# 02_Power.net
KiCad netlist of a schematic drawn in Altium Designer
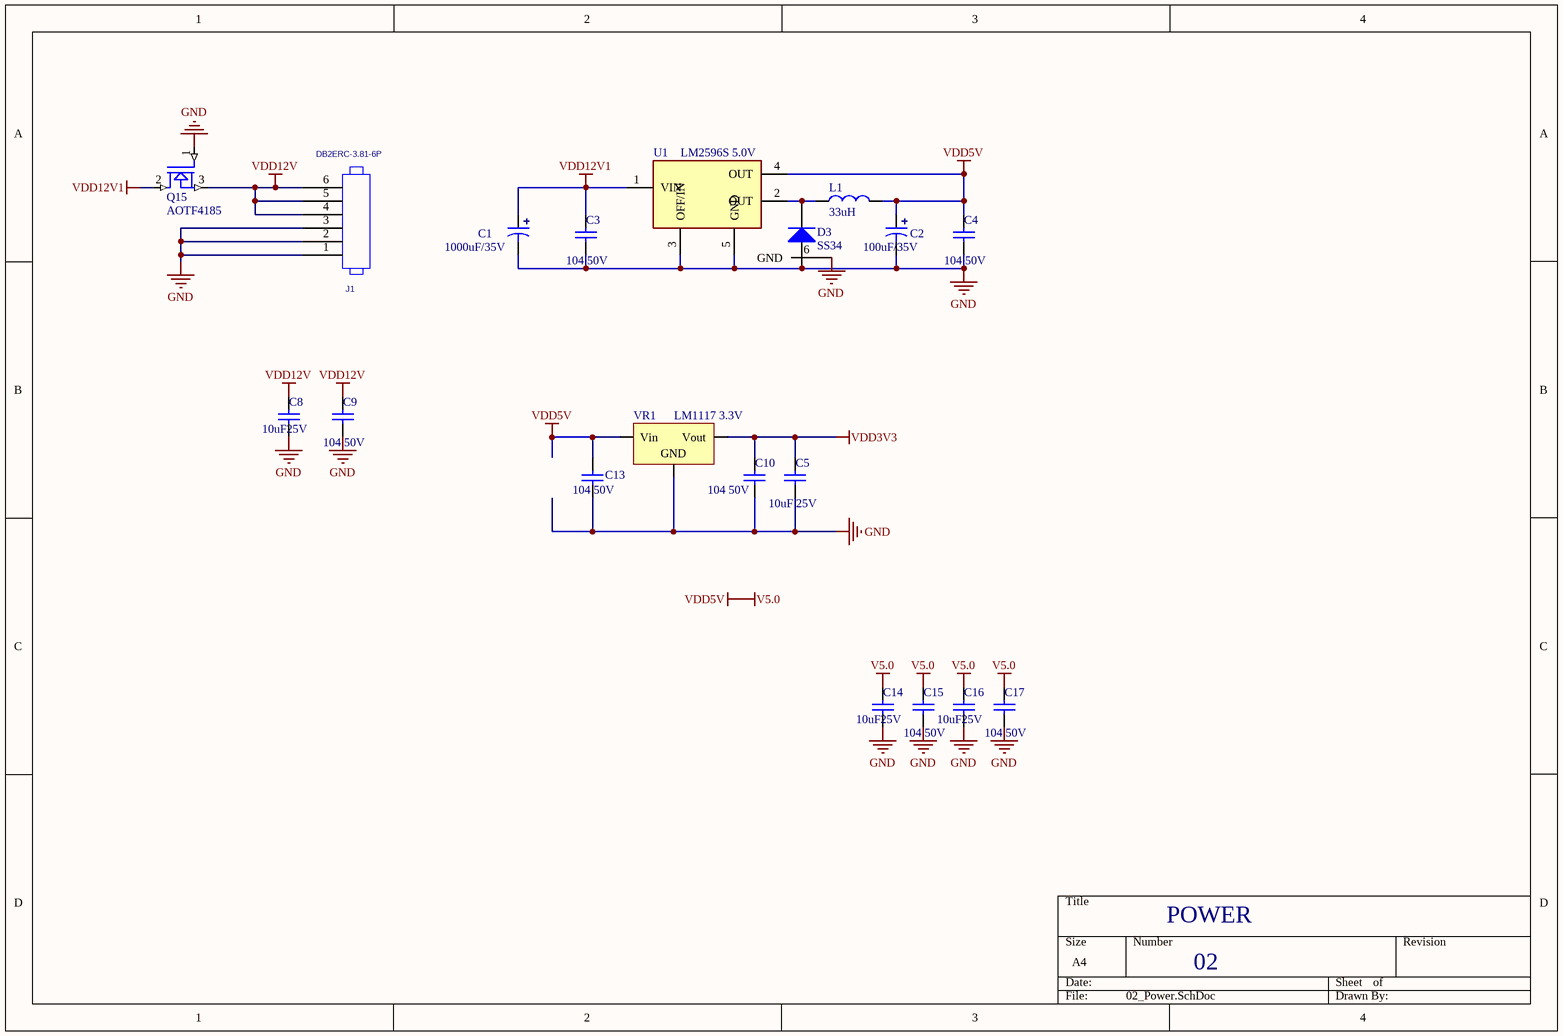
[diagram p0: 02_Power.SchDoc]

(export (version "E")
  (design (tool "Eeschema 10.0.6"))
  (components
    (comp (ref "C1")
      (value "1000uF/35V")
      (footprint "10*16")
      (description "电解电容")
      (libsource (lib "XiaoyI") (part "CAP2"))
    )
    (comp (ref "C2")
      (value "100uF/35V")
      (footprint "6*8")
      (description "电解电容")
      (libsource (lib "XiaoyI") (part "CAP2"))
    )
    (comp (ref "C3")
      (value "104 50V")
      (footprint "SMD-0805C")
      (description "贴片电容 10%")
      (libsource (lib "XiaoyI") (part "CAP4"))
    )
    (comp (ref "C4")
      (value "104 50V")
      (footprint "SMD-0805C")
      (description "贴片电容 10%")
      (libsource (lib "XiaoyI") (part "CAP4"))
    )
    (comp (ref "C5")
      (value "10uF 25V")
      (footprint "SMD-0603C")
      (description "贴片电容 20%")
      (libsource (lib "XiaoyI") (part "CAP4"))
    )
    (comp (ref "C8")
      (value "10uF25V")
      (footprint "SMD-0603C")
      (description "贴片电容 10%")
      (libsource (lib "XiaoyI") (part "CAP4"))
    )
    (comp (ref "C9")
      (value "104 50V")
      (footprint "SMD-0603C")
      (description "贴片电容 10%")
      (libsource (lib "XiaoyI") (part "CAP4"))
    )
    (comp (ref "C10")
      (value "104 50V")
      (footprint "SMD-0603C")
      (description "贴片电容 10%")
      (libsource (lib "XiaoyI") (part "CAP4"))
    )
    (comp (ref "C13")
      (value "104 50V")
      (footprint "SMD-0603C")
      (description "贴片电容 10%")
      (libsource (lib "XiaoyI") (part "CAP4"))
    )
    (comp (ref "C14")
      (value "10uF25V")
      (footprint "SMD-0603C")
      (description "贴片电容 20%")
      (libsource (lib "XiaoyI") (part "CAP4"))
    )
    (comp (ref "C15")
      (value "104 50V")
      (footprint "SMD-0603C")
      (description "贴片电容 20%")
      (libsource (lib "XiaoyI") (part "CAP4"))
    )
    (comp (ref "C16")
      (value "10uF25V")
      (footprint "SMD-0603C")
      (description "贴片电容 20%")
      (libsource (lib "XiaoyI") (part "CAP4"))
    )
    (comp (ref "C17")
      (value "104 50V")
      (footprint "SMD-0603C")
      (description "贴片电容 20%")
      (libsource (lib "XiaoyI") (part "CAP4"))
    )
    (comp (ref "D3") (value "SS34") (footprint "SMA") (libsource (lib "Sch_library") (part "DIODE")))
    (comp (ref "J1")
      (value "DB2ERC-3.81-6P")
      (footprint "VH-AW-3.96*6P")
      (fields (field (name "Comment") "HEADER_6"))
      (libsource (lib "liujingtao_V1.0") (part "HEADER_6"))
    )
    (comp (ref "L1") (value "33uH") (footprint "CDRH-127") (libsource (lib "Sch_library") (part "IND")))
    (comp (ref "Q15")
      (value "AOTF4185")
      (footprint "to220")
      (description "MOSFET N")
      (libsource (lib "XiaoyI") (part "MOSFET N"))
    )
    (comp (ref "U1")
      (value "LM2596S 5.0V")
      (footprint "TO-263-5")
      (libsource (lib "Sch_library") (part "LM2596"))
    )
    (comp (ref "VR1")
      (value "LM1117 3.3V")
      (footprint "SOT223")
      (description "三端稳压器")
      (libsource (lib "XiaoyI") (part "LM1117"))
    )
  )
  (nets
    (net (code "1") (name "GND") (class "Default")
      (node (ref "C1") (pin "2") (pinfunction "2_2") (pintype "passive"))
      (node (ref "C10") (pin "1") (pinfunction "1_1") (pintype "passive"))
      (node (ref "C13") (pin "1") (pinfunction "1_1") (pintype "passive"))
      (node (ref "C14") (pin "1") (pinfunction "1_1") (pintype "passive"))
      (node (ref "C15") (pin "1") (pinfunction "1_1") (pintype "passive"))
      (node (ref "C16") (pin "1") (pinfunction "1_1") (pintype "passive"))
      (node (ref "C17") (pin "1") (pinfunction "1_1") (pintype "passive"))
      (node (ref "C2") (pin "2") (pinfunction "2_2") (pintype "passive"))
      (node (ref "C3") (pin "1") (pinfunction "1_1") (pintype "passive"))
      (node (ref "C4") (pin "1") (pinfunction "1_1") (pintype "passive"))
      (node (ref "C5") (pin "1") (pinfunction "1_1") (pintype "passive"))
      (node (ref "C8") (pin "1") (pinfunction "1_1") (pintype "passive"))
      (node (ref "C9") (pin "1") (pinfunction "1_1") (pintype "passive"))
      (node (ref "D3") (pin "1") (pinfunction "A_1") (pintype "passive"))
      (node (ref "J1") (pin "1") (pinfunction "1_1") (pintype "passive"))
      (node (ref "J1") (pin "2") (pinfunction "2_2") (pintype "passive"))
      (node (ref "J1") (pin "3") (pinfunction "3_3") (pintype "passive"))
      (node (ref "Q15") (pin "1") (pinfunction "G_1") (pintype "input"))
      (node (ref "U1") (pin "3") (pinfunction "OFF/IN_3") (pintype "passive"))
      (node (ref "U1") (pin "5") (pinfunction "GND_5") (pintype "passive"))
      (node (ref "U1") (pin "6") (pinfunction "GND_6") (pintype "passive"))
      (node (ref "VR1") (pin "1") (pinfunction "GND_1") (pintype "passive"))
    )
    (net (code "2") (name "Net-(D3-K)") (class "Default")
      (node (ref "D3") (pin "2") (pinfunction "K_2") (pintype "passive"))
      (node (ref "L1") (pin "1") (pinfunction "1_1") (pintype "passive"))
      (node (ref "U1") (pin "2") (pinfunction "OUT_2") (pintype "passive"))
    )
    (net (code "3") (name "V5.0") (class "Default")
      (node (ref "C13") (pin "2") (pinfunction "2_2") (pintype "passive"))
      (node (ref "C14") (pin "2") (pinfunction "2_2") (pintype "passive"))
      (node (ref "C15") (pin "2") (pinfunction "2_2") (pintype "passive"))
      (node (ref "C16") (pin "2") (pinfunction "2_2") (pintype "passive"))
      (node (ref "C17") (pin "2") (pinfunction "2_2") (pintype "passive"))
      (node (ref "C2") (pin "1") (pinfunction "1_1") (pintype "passive"))
      (node (ref "C4") (pin "2") (pinfunction "2_2") (pintype "passive"))
      (node (ref "L1") (pin "2") (pinfunction "2_2") (pintype "passive"))
      (node (ref "U1") (pin "4") (pinfunction "OUT_4") (pintype "passive"))
      (node (ref "VR1") (pin "3") (pinfunction "Vin_3") (pintype "passive"))
    )
    (net (code "4") (name "VDD3V3") (class "Default")
      (node (ref "C10") (pin "2") (pinfunction "2_2") (pintype "passive"))
      (node (ref "C5") (pin "2") (pinfunction "2_2") (pintype "passive"))
      (node (ref "VR1") (pin "2") (pinfunction "Vout_2") (pintype "passive"))
    )
    (net (code "5") (name "VDD12V") (class "Default")
      (node (ref "C8") (pin "2") (pinfunction "2_2") (pintype "passive"))
      (node (ref "C9") (pin "2") (pinfunction "2_2") (pintype "passive"))
      (node (ref "J1") (pin "4") (pinfunction "4_4") (pintype "passive"))
      (node (ref "J1") (pin "5") (pinfunction "5_5") (pintype "passive"))
      (node (ref "J1") (pin "6") (pinfunction "6_6") (pintype "passive"))
      (node (ref "Q15") (pin "3") (pinfunction "S_3") (pintype "output"))
    )
    (net (code "6") (name "VDD12V1") (class "Default")
      (node (ref "C1") (pin "1") (pinfunction "1_1") (pintype "passive"))
      (node (ref "C3") (pin "2") (pinfunction "2_2") (pintype "passive"))
      (node (ref "Q15") (pin "2") (pinfunction "D_2") (pintype "input"))
      (node (ref "U1") (pin "1") (pinfunction "VIN_1") (pintype "passive"))
    )
  )
)
